# EEPROM.net
KiCad netlist of a schematic drawn in Altium Designer
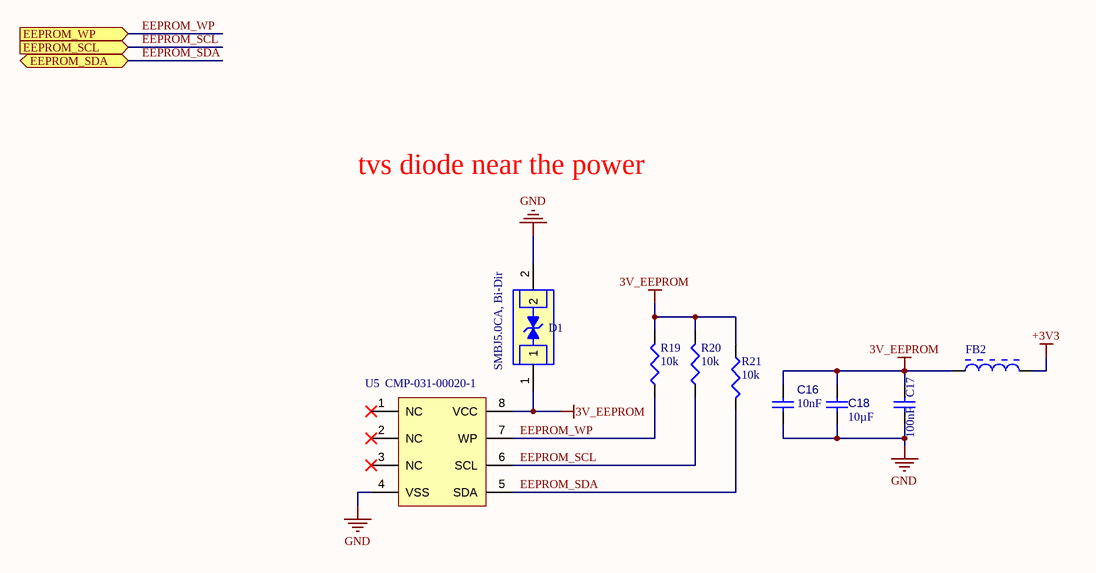
[diagram p0: EEPROM.SchDoc]

(export (version "E")
  (design (tool "Eeschema 10.0.6"))
  (components
    (comp (ref "C16")
      (value "10nF")
      (footprint "C0603")
      (description "0603 10nF 50 V ±10 % Tolerance X7R Surface Mount Multilayer Ceramic Capacitor")
      (fields (field (name "TOLERANCE") "10%") (field (name "MANUFACTURER") "Kyocera AVX"))
      (libsource (lib "Kish Spark") (part "CAP-NP-2"))
    )
    (comp (ref "C17")
      (value "100nF")
      (footprint "C0603")
      (description "YAGEO - CC0603KRX7R8BB104 - CERAMIC CAPACITOR, 0.1UF, 25V, X7R, 10%, 0603, FULL REEL")
      (fields
        (field (name "TOLERANCE") "10%")
        (field (name "VOLTAGE") "25V")
        (field (name "SOURCE") "PTZLib.SchLib")
      )
      (libsource (lib "Kish Spark") (part "CAP-NP-2"))
    )
    (comp (ref "C18")
      (value "10µF")
      (footprint "0805")
      (description "Ceramic Capacitor, 10UF, 6.3V, X5R, 10%, 0805, Full Reel")
      (fields
        (field (name "MANUFACTURER") "KEMET")
        (field (name "MANUFACTURER PART NUMBER") "C0805C106K9PACTU")
      )
      (libsource (lib "Kish Spark") (part "CAP-NP-2"))
    )
    (comp (ref "D1")
      (value "SMBJ5.0CA, Bi-Dir")
      (footprint "SMB (DO-214AA)")
      (description "Diode TVS Single Bi-Dir 5V 600W 2-Pin SMBJ")
      (fields
        (field (name "MANUFACTURER") "Bourns")
        (field (name "MANUFACTURER PART NUMBER") "SMBJ5.0CA")
        (field (name "SOURCE") "PTZ.SCHLIB")
      )
      (libsource (lib "Kish Spark") (part "SMBJ5.0CA"))
    )
    (comp (ref "FB2")
      (value "CMP-006-00051-1")
      (footprint "R0603")
      (description "Ferrite Beads 0603 60ohm")
      (fields (field (name "TOLERANCE") "25%") (field (name "SOURCE") "PTZLib.SchLib"))
      (libsource (lib "Kish Spark") (part "FerriteBead"))
    )
    (comp (ref "R19")
      (value "10k")
      (footprint "R0603")
      (description "Res Thick Film 0603 10K Ohm 5% 1/10W 200ppm/C Molded SMD SMD Paper T/R")
      (fields
        (field (name "TOLERANCE") "5%")
        (field (name "Comment") "CRCW060310K0JNEA")
        (field (name "SOURCE") "PTZLib.SchLib")
      )
      (libsource (lib "Kish Spark") (part "RN73R1JTTD3302F10"))
    )
    (comp (ref "R20")
      (value "10k")
      (footprint "R0603")
      (description "Res Thick Film 0603 10K Ohm 5% 1/10W 200ppm/C Molded SMD SMD Paper T/R")
      (fields
        (field (name "TOLERANCE") "5%")
        (field (name "Comment") "CRCW060310K0JNEA")
        (field (name "SOURCE") "PTZLib.SchLib")
      )
      (libsource (lib "Kish Spark") (part "RN73R1JTTD3302F10"))
    )
    (comp (ref "R21")
      (value "10k")
      (footprint "R0603")
      (description "Res Thick Film 0603 10K Ohm 5% 1/10W 200ppm/C Molded SMD SMD Paper T/R")
      (fields
        (field (name "TOLERANCE") "5%")
        (field (name "Comment") "CRCW060310K0JNEA")
        (field (name "SOURCE") "PTZLib.SchLib")
      )
      (libsource (lib "Kish Spark") (part "RN73R1JTTD3302F10"))
    )
    (comp (ref "U5")
      (value "CMP-031-00020-1")
      (footprint "NV24C16UV")
      (description "EEPROM Serial 16-Kb I2C - Automotive Grade")
      (fields
        (field (name "MANUFACTURER") "ON Semiconductor")
        (field (name "MANUFACTURER PART NUMBER") "NV24C16MUW3VLTBG")
      )
      (libsource (lib "Kish Spark") (part "NV24C16MUW3VLTBG"))
    )
  )
  (nets
    (net (code "1") (name "+3V3") (class "Default")
      (node (ref "FB2") (pin "2") (pinfunction "2_2") (pintype "passive"))
    )
    (net (code "2") (name "/EEPROM_SCL") (class "Default")
      (node (ref "R20") (pin "1") (pinfunction "1_1") (pintype "passive"))
      (node (ref "U5") (pin "6") (pinfunction "SCL_6") (pintype "passive"))
    )
    (net (code "3") (name "/EEPROM_SDA") (class "Default")
      (node (ref "R21") (pin "2") (pinfunction "2_2") (pintype "passive"))
      (node (ref "U5") (pin "5") (pinfunction "SDA_5") (pintype "passive"))
    )
    (net (code "4") (name "/EEPROM_WP") (class "Default")
      (node (ref "R19") (pin "1") (pinfunction "1_1") (pintype "passive"))
      (node (ref "U5") (pin "7") (pinfunction "WP_7") (pintype "passive"))
    )
    (net (code "5") (name "3V_EEPROM") (class "Default")
      (node (ref "C16") (pin "2") (pinfunction "2_2") (pintype "passive"))
      (node (ref "C17") (pin "1") (pinfunction "1_1") (pintype "passive"))
      (node (ref "C18") (pin "2") (pinfunction "2_2") (pintype "passive"))
      (node (ref "D1") (pin "1") (pinfunction "1_1") (pintype "passive"))
      (node (ref "FB2") (pin "1") (pinfunction "1_1") (pintype "passive"))
      (node (ref "R19") (pin "2") (pinfunction "2_2") (pintype "passive"))
      (node (ref "R20") (pin "2") (pinfunction "2_2") (pintype "passive"))
      (node (ref "R21") (pin "1") (pinfunction "1_1") (pintype "passive"))
      (node (ref "U5") (pin "8") (pinfunction "VCC_8") (pintype "passive"))
    )
    (net (code "6") (name "GND") (class "Default")
      (node (ref "C16") (pin "1") (pinfunction "1_1") (pintype "passive"))
      (node (ref "C17") (pin "2") (pinfunction "2_2") (pintype "passive"))
      (node (ref "C18") (pin "1") (pinfunction "1_1") (pintype "passive"))
      (node (ref "D1") (pin "2") (pinfunction "2_2") (pintype "passive"))
      (node (ref "U5") (pin "4") (pinfunction "VSS_4") (pintype "passive"))
    )
    (net (code "7") (name "unconnected-(U5-NC-Pad1)") (class "Default")
      (node (ref "U5") (pin "1") (pinfunction "NC_1") (pintype "passive+no_connect"))
    )
    (net (code "8") (name "unconnected-(U5-NC-Pad2)") (class "Default")
      (node (ref "U5") (pin "2") (pinfunction "NC_2") (pintype "passive+no_connect"))
    )
    (net (code "9") (name "unconnected-(U5-NC-Pad3)") (class "Default")
      (node (ref "U5") (pin "3") (pinfunction "NC_3") (pintype "passive+no_connect"))
    )
  )
)
